# base_unit_pcb_v1.net
KiCad netlist of a schematic drawn in EAGLE
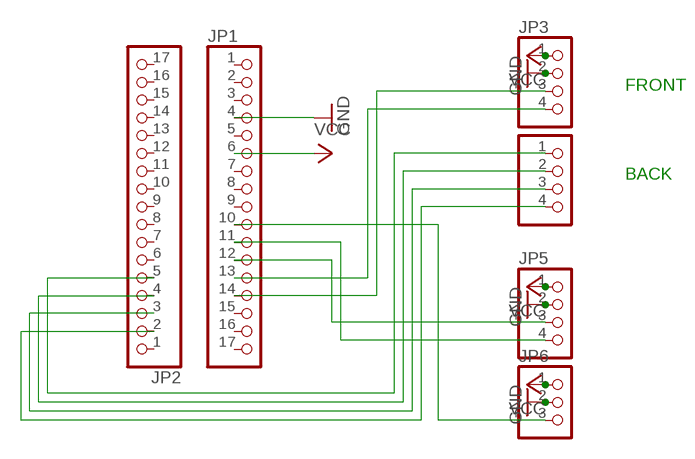
[diagram p0: schematic, sheet 1]

(export (version "E")
  (design (tool "Eeschema 10.0.6"))
  (components
    (comp (ref "JP1")
      (value "PINHD-1X17")
      (footprint "eagle-import:1X17")
      (libsource (lib "eagle-import") (part "PINHD-1X17"))
    )
    (comp (ref "JP2")
      (value "PINHD-1X17")
      (footprint "eagle-import:1X17")
      (libsource (lib "eagle-import") (part "PINHD-1X17"))
    )
    (comp (ref "JP3")
      (value "PINHD-1X4")
      (footprint "eagle-import:1X04")
      (libsource (lib "eagle-import") (part "PINHD-1X4"))
    )
    (comp (ref "JP4")
      (value "PINHD-1X4")
      (footprint "eagle-import:1X04")
      (libsource (lib "eagle-import") (part "PINHD-1X4"))
    )
    (comp (ref "JP5")
      (value "PINHD-1X4")
      (footprint "eagle-import:1X04")
      (libsource (lib "eagle-import") (part "PINHD-1X4"))
    )
    (comp (ref "JP6")
      (value "PINHD-1X3")
      (footprint "eagle-import:1X03")
      (libsource (lib "eagle-import") (part "PINHD-1X3"))
    )
  )
  (nets
    (net (code "1") (name "GND") (class "Default")
      (node (ref "JP1") (pin "4") (pinfunction "4_4") (pintype "passive"))
      (node (ref "JP3") (pin "2") (pinfunction "2_2") (pintype "passive"))
      (node (ref "JP5") (pin "2") (pinfunction "2_2") (pintype "passive"))
      (node (ref "JP6") (pin "2") (pinfunction "2_2") (pintype "passive"))
    )
    (net (code "2") (name "Net-(JP1-Pad10)") (class "Default")
      (node (ref "JP1") (pin "10") (pinfunction "10_10") (pintype "passive"))
      (node (ref "JP6") (pin "3") (pinfunction "3_3") (pintype "passive"))
    )
    (net (code "3") (name "Net-(JP1-Pad11)") (class "Default")
      (node (ref "JP1") (pin "11") (pinfunction "11_11") (pintype "passive"))
      (node (ref "JP5") (pin "4") (pinfunction "4_4") (pintype "passive"))
    )
    (net (code "4") (name "Net-(JP1-Pad12)") (class "Default")
      (node (ref "JP1") (pin "12") (pinfunction "12_12") (pintype "passive"))
      (node (ref "JP5") (pin "3") (pinfunction "3_3") (pintype "passive"))
    )
    (net (code "5") (name "Net-(JP1-Pad13)") (class "Default")
      (node (ref "JP1") (pin "13") (pinfunction "13_13") (pintype "passive"))
      (node (ref "JP3") (pin "4") (pinfunction "4_4") (pintype "passive"))
    )
    (net (code "6") (name "Net-(JP1-Pad14)") (class "Default")
      (node (ref "JP1") (pin "14") (pinfunction "14_14") (pintype "passive"))
      (node (ref "JP3") (pin "3") (pinfunction "3_3") (pintype "passive"))
    )
    (net (code "7") (name "Net-(JP2-Pad2)") (class "Default")
      (node (ref "JP2") (pin "2") (pinfunction "2_2") (pintype "passive"))
      (node (ref "JP4") (pin "4") (pinfunction "4_4") (pintype "passive"))
    )
    (net (code "8") (name "Net-(JP2-Pad3)") (class "Default")
      (node (ref "JP2") (pin "3") (pinfunction "3_3") (pintype "passive"))
      (node (ref "JP4") (pin "3") (pinfunction "3_3") (pintype "passive"))
    )
    (net (code "9") (name "Net-(JP2-Pad4)") (class "Default")
      (node (ref "JP2") (pin "4") (pinfunction "4_4") (pintype "passive"))
      (node (ref "JP4") (pin "2") (pinfunction "2_2") (pintype "passive"))
    )
    (net (code "10") (name "Net-(JP2-Pad5)") (class "Default")
      (node (ref "JP2") (pin "5") (pinfunction "5_5") (pintype "passive"))
      (node (ref "JP4") (pin "1") (pinfunction "1_1") (pintype "passive"))
    )
    (net (code "11") (name "VCC") (class "Default")
      (node (ref "JP1") (pin "6") (pinfunction "6_6") (pintype "passive"))
      (node (ref "JP3") (pin "1") (pinfunction "1_1") (pintype "passive"))
      (node (ref "JP5") (pin "1") (pinfunction "1_1") (pintype "passive"))
      (node (ref "JP6") (pin "1") (pinfunction "1_1") (pintype "passive"))
    )
    (net (code "12") (name "unconnected-(JP1-Pad1)") (class "Default")
      (node (ref "JP1") (pin "1") (pinfunction "1_1") (pintype "passive"))
    )
    (net (code "13") (name "unconnected-(JP1-Pad2)") (class "Default")
      (node (ref "JP1") (pin "2") (pinfunction "2_2") (pintype "passive"))
    )
    (net (code "14") (name "unconnected-(JP1-Pad3)") (class "Default")
      (node (ref "JP1") (pin "3") (pinfunction "3_3") (pintype "passive"))
    )
    (net (code "15") (name "unconnected-(JP1-Pad5)") (class "Default")
      (node (ref "JP1") (pin "5") (pinfunction "5_5") (pintype "passive"))
    )
    (net (code "16") (name "unconnected-(JP1-Pad7)") (class "Default")
      (node (ref "JP1") (pin "7") (pinfunction "7_7") (pintype "passive"))
    )
    (net (code "17") (name "unconnected-(JP1-Pad8)") (class "Default")
      (node (ref "JP1") (pin "8") (pinfunction "8_8") (pintype "passive"))
    )
    (net (code "18") (name "unconnected-(JP1-Pad9)") (class "Default")
      (node (ref "JP1") (pin "9") (pinfunction "9_9") (pintype "passive"))
    )
    (net (code "19") (name "unconnected-(JP1-Pad15)") (class "Default")
      (node (ref "JP1") (pin "15") (pinfunction "15_15") (pintype "passive"))
    )
    (net (code "20") (name "unconnected-(JP1-Pad16)") (class "Default")
      (node (ref "JP1") (pin "16") (pinfunction "16_16") (pintype "passive"))
    )
    (net (code "21") (name "unconnected-(JP1-Pad17)") (class "Default")
      (node (ref "JP1") (pin "17") (pinfunction "17_17") (pintype "passive"))
    )
    (net (code "22") (name "unconnected-(JP2-Pad1)") (class "Default")
      (node (ref "JP2") (pin "1") (pinfunction "1_1") (pintype "passive"))
    )
    (net (code "23") (name "unconnected-(JP2-Pad6)") (class "Default")
      (node (ref "JP2") (pin "6") (pinfunction "6_6") (pintype "passive"))
    )
    (net (code "24") (name "unconnected-(JP2-Pad7)") (class "Default")
      (node (ref "JP2") (pin "7") (pinfunction "7_7") (pintype "passive"))
    )
    (net (code "25") (name "unconnected-(JP2-Pad8)") (class "Default")
      (node (ref "JP2") (pin "8") (pinfunction "8_8") (pintype "passive"))
    )
    (net (code "26") (name "unconnected-(JP2-Pad9)") (class "Default")
      (node (ref "JP2") (pin "9") (pinfunction "9_9") (pintype "passive"))
    )
    (net (code "27") (name "unconnected-(JP2-Pad10)") (class "Default")
      (node (ref "JP2") (pin "10") (pinfunction "10_10") (pintype "passive"))
    )
    (net (code "28") (name "unconnected-(JP2-Pad11)") (class "Default")
      (node (ref "JP2") (pin "11") (pinfunction "11_11") (pintype "passive"))
    )
    (net (code "29") (name "unconnected-(JP2-Pad12)") (class "Default")
      (node (ref "JP2") (pin "12") (pinfunction "12_12") (pintype "passive"))
    )
    (net (code "30") (name "unconnected-(JP2-Pad13)") (class "Default")
      (node (ref "JP2") (pin "13") (pinfunction "13_13") (pintype "passive"))
    )
    (net (code "31") (name "unconnected-(JP2-Pad14)") (class "Default")
      (node (ref "JP2") (pin "14") (pinfunction "14_14") (pintype "passive"))
    )
    (net (code "32") (name "unconnected-(JP2-Pad15)") (class "Default")
      (node (ref "JP2") (pin "15") (pinfunction "15_15") (pintype "passive"))
    )
    (net (code "33") (name "unconnected-(JP2-Pad16)") (class "Default")
      (node (ref "JP2") (pin "16") (pinfunction "16_16") (pintype "passive"))
    )
    (net (code "34") (name "unconnected-(JP2-Pad17)") (class "Default")
      (node (ref "JP2") (pin "17") (pinfunction "17_17") (pintype "passive"))
    )
  )
)
